# OSSC_HDMI_Audio_v1_5_A4b.net
KiCad netlist of a schematic drawn in EAGLE
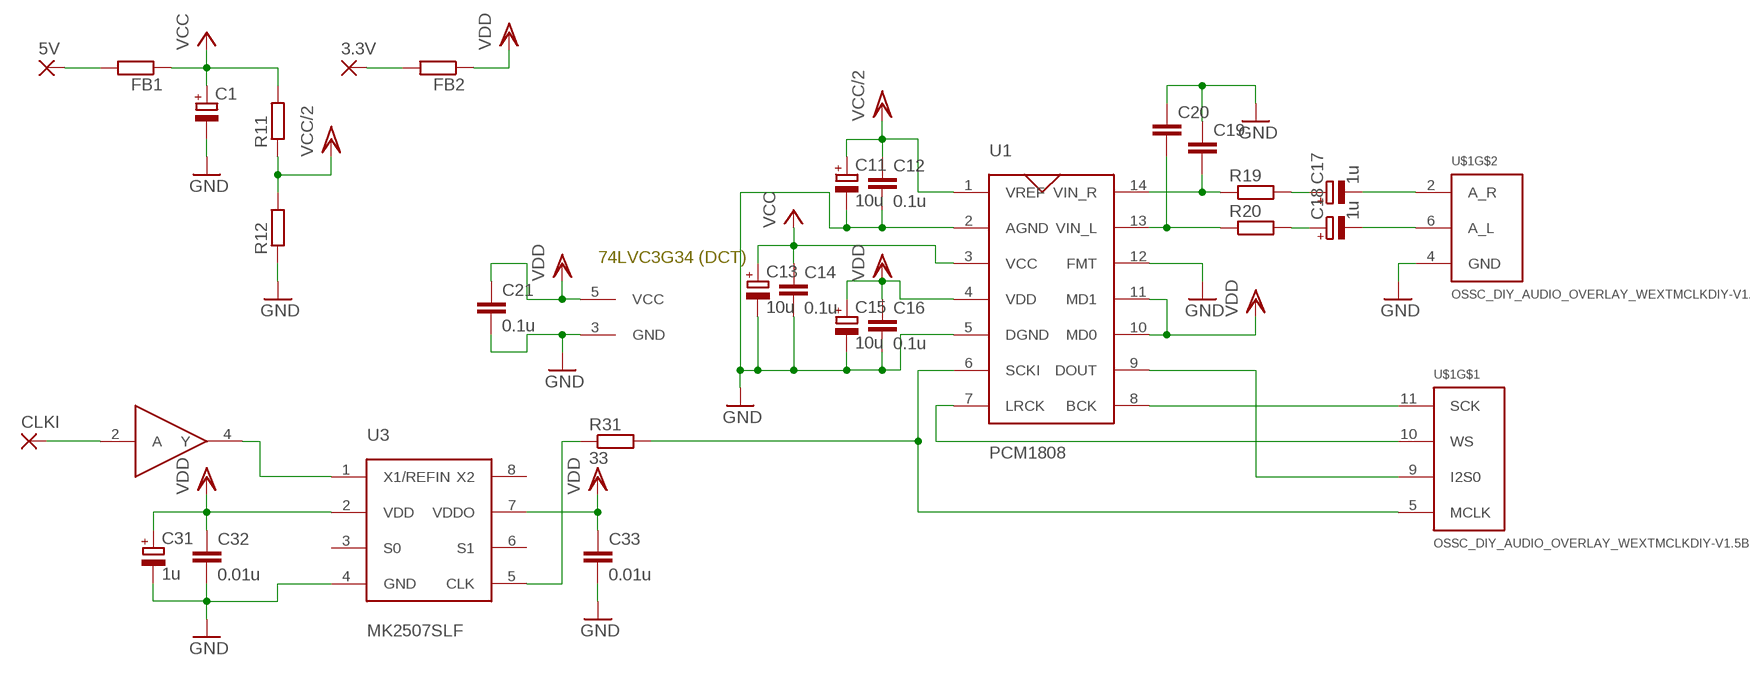
[diagram p0: schematic, sheet 1]

(export (version "E")
  (design (tool "Eeschema 10.0.6"))
  (components
    (comp (ref "3.3V")
      (value "SMD2")
      (footprint "eagle-import:SMD1,27-2,54")
      (libsource (lib "eagle-import") (part "SMD2"))
    )
    (comp (ref "5V")
      (value "SMD2")
      (footprint "eagle-import:SMD1,27-2,54")
      (libsource (lib "eagle-import") (part "SMD2"))
    )
    (comp (ref "C1")
      (value "CPOL-EUSMCC")
      (footprint "eagle-import:SMC_C")
      (libsource (lib "eagle-import") (part "CPOL-EUSMCC"))
    )
    (comp (ref "C11")
      (value "10u")
      (footprint "eagle-import:SMC_A")
      (libsource (lib "eagle-import") (part "CPOL-EUSMCA"))
    )
    (comp (ref "C12")
      (value "0.1u")
      (footprint "eagle-import:C0603")
      (libsource (lib "eagle-import") (part "C-EUC0603"))
    )
    (comp (ref "C13")
      (value "10u")
      (footprint "eagle-import:SMC_A")
      (libsource (lib "eagle-import") (part "CPOL-EUSMCA"))
    )
    (comp (ref "C14")
      (value "0.1u")
      (footprint "eagle-import:C0603")
      (libsource (lib "eagle-import") (part "C-EUC0603"))
    )
    (comp (ref "C15")
      (value "10u")
      (footprint "eagle-import:SMC_A")
      (libsource (lib "eagle-import") (part "CPOL-EUSMCA"))
    )
    (comp (ref "C16")
      (value "0.1u")
      (footprint "eagle-import:C0603")
      (libsource (lib "eagle-import") (part "C-EUC0603"))
    )
    (comp (ref "C17")
      (value "1u")
      (footprint "eagle-import:SMC_A")
      (libsource (lib "eagle-import") (part "CPOL-EUSMCA"))
    )
    (comp (ref "C18")
      (value "1u")
      (footprint "eagle-import:SMC_A")
      (libsource (lib "eagle-import") (part "CPOL-EUSMCA"))
    )
    (comp (ref "C19")
      (value "C-EUC0603")
      (footprint "eagle-import:C0603")
      (libsource (lib "eagle-import") (part "C-EUC0603"))
    )
    (comp (ref "C20")
      (value "C-EUC0603")
      (footprint "eagle-import:C0603")
      (libsource (lib "eagle-import") (part "C-EUC0603"))
    )
    (comp (ref "C21")
      (value "0.1u")
      (footprint "eagle-import:C0603")
      (libsource (lib "eagle-import") (part "C-EUC0603"))
    )
    (comp (ref "C31")
      (value "1u")
      (footprint "eagle-import:SMC_A")
      (libsource (lib "eagle-import") (part "CPOL-EUSMCA"))
    )
    (comp (ref "C32")
      (value "0.01u")
      (footprint "eagle-import:C0603")
      (libsource (lib "eagle-import") (part "C-EUC0603"))
    )
    (comp (ref "C33")
      (value "0.01u")
      (footprint "eagle-import:C0603")
      (libsource (lib "eagle-import") (part "C-EUC0603"))
    )
    (comp (ref "CLKI")
      (value "SMD2")
      (footprint "eagle-import:SMD1,27-2,54")
      (libsource (lib "eagle-import") (part "SMD2"))
    )
    (comp (ref "FB1")
      (value "R-EU_R0603")
      (footprint "eagle-import:R0603")
      (libsource (lib "eagle-import") (part "R-EU_R0603"))
    )
    (comp (ref "FB2")
      (value "R-EU_R0603")
      (footprint "eagle-import:R0603")
      (libsource (lib "eagle-import") (part "R-EU_R0603"))
    )
    (comp (ref "R11")
      (value "R-EU_R0603")
      (footprint "eagle-import:R0603")
      (libsource (lib "eagle-import") (part "R-EU_R0603"))
    )
    (comp (ref "R12")
      (value "R-EU_R0603")
      (footprint "eagle-import:R0603")
      (libsource (lib "eagle-import") (part "R-EU_R0603"))
    )
    (comp (ref "R19")
      (value "R-EU_R0603")
      (footprint "eagle-import:R0603")
      (libsource (lib "eagle-import") (part "R-EU_R0603"))
    )
    (comp (ref "R20")
      (value "R-EU_R0603")
      (footprint "eagle-import:R0603")
      (libsource (lib "eagle-import") (part "R-EU_R0603"))
    )
    (comp (ref "R31")
      (value "33")
      (footprint "eagle-import:R0603")
      (libsource (lib "eagle-import") (part "R-EU_R0603"))
    )
    (comp (ref "U$1")
      (value "OSSC_DIY_AUDIO_OVERLAY_WEXTMCLKDIY-V1.5B")
      (footprint "eagle-import:OSSC_OVERLAY_V1.5B_WEXTMCLK")
      (libsource (lib "eagle-import") (part "OSSC_DIY_AUDIO_OVERLAY_WEXTMCLKDIY-V1.5B"))
    )
    (comp (ref "U1")
      (value "PCM1808")
      (footprint "eagle-import:PCM1808")
      (libsource (lib "eagle-import") (part "PCM1808"))
    )
    (comp (ref "U2")
      (value "74LVC1G34")
      (footprint "eagle-import:74LVC1G34DCK")
      (libsource (lib "eagle-import") (part "74LVC1G34"))
    )
    (comp (ref "U3")
      (value "MK2507SLF")
      (footprint "eagle-import:SOIC8")
      (libsource (lib "eagle-import") (part "MK2507SLF"))
    )
  )
  (nets
    (net (code "1") (name "GND") (class "Default")
      (node (ref "C1") (pin "-") (pinfunction "-_-") (pintype "passive"))
      (node (ref "C11") (pin "-") (pinfunction "-_-") (pintype "passive"))
      (node (ref "C12") (pin "2") (pinfunction "2_2") (pintype "passive"))
      (node (ref "C13") (pin "-") (pinfunction "-_-") (pintype "passive"))
      (node (ref "C14") (pin "2") (pinfunction "2_2") (pintype "passive"))
      (node (ref "C15") (pin "-") (pinfunction "-_-") (pintype "passive"))
      (node (ref "C16") (pin "2") (pinfunction "2_2") (pintype "passive"))
      (node (ref "C19") (pin "1") (pinfunction "1_1") (pintype "passive"))
      (node (ref "C20") (pin "1") (pinfunction "1_1") (pintype "passive"))
      (node (ref "C21") (pin "2") (pinfunction "2_2") (pintype "passive"))
      (node (ref "C31") (pin "-") (pinfunction "-_-") (pintype "passive"))
      (node (ref "C32") (pin "2") (pinfunction "2_2") (pintype "passive"))
      (node (ref "C33") (pin "2") (pinfunction "2_2") (pintype "passive"))
      (node (ref "R12") (pin "1") (pinfunction "1_1") (pintype "passive"))
      (node (ref "U$1") (pin "4") (pinfunction "GND_4") (pintype "bidirectional"))
      (node (ref "U1") (pin "12") (pinfunction "FMT_12") (pintype "bidirectional"))
      (node (ref "U1") (pin "2") (pinfunction "AGND_2") (pintype "bidirectional"))
      (node (ref "U1") (pin "5") (pinfunction "DGND_5") (pintype "bidirectional"))
      (node (ref "U2") (pin "3") (pinfunction "GND_3") (pintype "bidirectional"))
      (node (ref "U3") (pin "4") (pinfunction "GND_4") (pintype "bidirectional"))
    )
    (net (code "2") (name "Net-(3.3V-P)") (class "Default")
      (node (ref "3.3V") (pin "1") (pinfunction "P_1") (pintype "passive"))
      (node (ref "FB2") (pin "2") (pinfunction "2_2") (pintype "passive"))
    )
    (net (code "3") (name "Net-(5V-P)") (class "Default")
      (node (ref "5V") (pin "1") (pinfunction "P_1") (pintype "passive"))
      (node (ref "FB1") (pin "2") (pinfunction "2_2") (pintype "passive"))
    )
    (net (code "4") (name "Net-(C17-Pad+)") (class "Default")
      (node (ref "C17") (pin "+") (pinfunction "+_+") (pintype "passive"))
      (node (ref "R19") (pin "2") (pinfunction "2_2") (pintype "passive"))
    )
    (net (code "5") (name "Net-(C18-Pad+)") (class "Default")
      (node (ref "C18") (pin "+") (pinfunction "+_+") (pintype "passive"))
      (node (ref "R20") (pin "2") (pinfunction "2_2") (pintype "passive"))
    )
    (net (code "6") (name "Net-(CLKI-P)") (class "Default")
      (node (ref "CLKI") (pin "1") (pinfunction "P_1") (pintype "passive"))
      (node (ref "U2") (pin "2") (pinfunction "A_2") (pintype "bidirectional"))
    )
    (net (code "7") (name "Net-(U$1A-I2S0)") (class "Default")
      (node (ref "U$1") (pin "9") (pinfunction "I2S0_9") (pintype "bidirectional"))
      (node (ref "U1") (pin "9") (pinfunction "DOUT_9") (pintype "bidirectional"))
    )
    (net (code "8") (name "Net-(U$1A-MCLK)") (class "Default")
      (node (ref "R31") (pin "2") (pinfunction "2_2") (pintype "passive"))
      (node (ref "U$1") (pin "5") (pinfunction "MCLK_5") (pintype "bidirectional"))
      (node (ref "U1") (pin "6") (pinfunction "SCKI_6") (pintype "bidirectional"))
    )
    (net (code "9") (name "Net-(U$1A-SCK)") (class "Default")
      (node (ref "U$1") (pin "11") (pinfunction "SCK_11") (pintype "bidirectional"))
      (node (ref "U1") (pin "8") (pinfunction "BCK_8") (pintype "bidirectional"))
    )
    (net (code "10") (name "Net-(U$1A-WS)") (class "Default")
      (node (ref "U$1") (pin "10") (pinfunction "WS_10") (pintype "bidirectional"))
      (node (ref "U1") (pin "7") (pinfunction "LRCK_7") (pintype "bidirectional"))
    )
    (net (code "11") (name "Net-(U$1B-A_L)") (class "Default")
      (node (ref "C18") (pin "-") (pinfunction "-_-") (pintype "passive"))
      (node (ref "U$1") (pin "6") (pinfunction "A_L_6") (pintype "bidirectional"))
    )
    (net (code "12") (name "Net-(U$1B-A_R)") (class "Default")
      (node (ref "C17") (pin "-") (pinfunction "-_-") (pintype "passive"))
      (node (ref "U$1") (pin "2") (pinfunction "A_R_2") (pintype "bidirectional"))
    )
    (net (code "13") (name "Net-(U1-VIN_L)") (class "Default")
      (node (ref "C20") (pin "2") (pinfunction "2_2") (pintype "passive"))
      (node (ref "R20") (pin "1") (pinfunction "1_1") (pintype "passive"))
      (node (ref "U1") (pin "13") (pinfunction "VIN_L_13") (pintype "bidirectional"))
    )
    (net (code "14") (name "Net-(U1-VIN_R)") (class "Default")
      (node (ref "C19") (pin "2") (pinfunction "2_2") (pintype "passive"))
      (node (ref "R19") (pin "1") (pinfunction "1_1") (pintype "passive"))
      (node (ref "U1") (pin "14") (pinfunction "VIN_R_14") (pintype "bidirectional"))
    )
    (net (code "15") (name "Net-(U2A-Y)") (class "Default")
      (node (ref "U2") (pin "4") (pinfunction "Y_4") (pintype "bidirectional"))
      (node (ref "U3") (pin "1") (pinfunction "X1/REFIN_1") (pintype "bidirectional"))
    )
    (net (code "16") (name "Net-(U3-CLK)") (class "Default")
      (node (ref "R31") (pin "1") (pinfunction "1_1") (pintype "passive"))
      (node (ref "U3") (pin "5") (pinfunction "CLK_5") (pintype "bidirectional"))
    )
    (net (code "17") (name "VCC") (class "Default")
      (node (ref "C1") (pin "+") (pinfunction "+_+") (pintype "passive"))
      (node (ref "C13") (pin "+") (pinfunction "+_+") (pintype "passive"))
      (node (ref "C14") (pin "1") (pinfunction "1_1") (pintype "passive"))
      (node (ref "FB1") (pin "1") (pinfunction "1_1") (pintype "passive"))
      (node (ref "R11") (pin "2") (pinfunction "2_2") (pintype "passive"))
      (node (ref "U1") (pin "3") (pinfunction "VCC_3") (pintype "bidirectional"))
    )
    (net (code "18") (name "VCC{slash}2") (class "Default")
      (node (ref "C11") (pin "+") (pinfunction "+_+") (pintype "passive"))
      (node (ref "C12") (pin "1") (pinfunction "1_1") (pintype "passive"))
      (node (ref "R11") (pin "1") (pinfunction "1_1") (pintype "passive"))
      (node (ref "R12") (pin "2") (pinfunction "2_2") (pintype "passive"))
      (node (ref "U1") (pin "1") (pinfunction "VREF_1") (pintype "bidirectional"))
    )
    (net (code "19") (name "VDD") (class "Default")
      (node (ref "C15") (pin "+") (pinfunction "+_+") (pintype "passive"))
      (node (ref "C16") (pin "1") (pinfunction "1_1") (pintype "passive"))
      (node (ref "C21") (pin "1") (pinfunction "1_1") (pintype "passive"))
      (node (ref "C31") (pin "+") (pinfunction "+_+") (pintype "passive"))
      (node (ref "C32") (pin "1") (pinfunction "1_1") (pintype "passive"))
      (node (ref "C33") (pin "1") (pinfunction "1_1") (pintype "passive"))
      (node (ref "FB2") (pin "1") (pinfunction "1_1") (pintype "passive"))
      (node (ref "U1") (pin "10") (pinfunction "MD0_10") (pintype "bidirectional"))
      (node (ref "U1") (pin "11") (pinfunction "MD1_11") (pintype "bidirectional"))
      (node (ref "U1") (pin "4") (pinfunction "VDD_4") (pintype "bidirectional"))
      (node (ref "U2") (pin "5") (pinfunction "VCC_5") (pintype "bidirectional"))
      (node (ref "U3") (pin "2") (pinfunction "VDD_2") (pintype "bidirectional"))
      (node (ref "U3") (pin "7") (pinfunction "VDDO_7") (pintype "bidirectional"))
    )
    (net (code "20") (name "unconnected-(U3-S0-Pad3)") (class "Default")
      (node (ref "U3") (pin "3") (pinfunction "S0_3") (pintype "bidirectional"))
    )
    (net (code "21") (name "unconnected-(U3-S1-Pad6)") (class "Default")
      (node (ref "U3") (pin "6") (pinfunction "S1_6") (pintype "bidirectional"))
    )
    (net (code "22") (name "unconnected-(U3-X2-Pad8)") (class "Default")
      (node (ref "U3") (pin "8") (pinfunction "X2_8") (pintype "bidirectional"))
    )
  )
)
